# simon_SMD.net
KiCad netlist of a schematic drawn in EAGLE
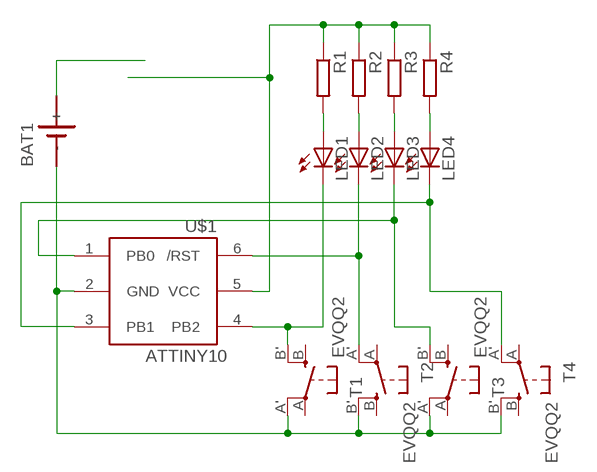
[diagram p0: schematic, sheet 1]

(export (version "E")
  (design (tool "Eeschema 10.0.6"))
  (components
    (comp (ref "BAT1")
      (value "SN2032")
      (footprint "eagle-import:SN2032")
      (libsource (lib "eagle-import") (part "SN2032"))
    )
    (comp (ref "LED1")
      (value "LEDCHIP-LED0805")
      (footprint "eagle-import:CHIP-LED0805")
      (libsource (lib "eagle-import") (part "LEDCHIP-LED0805"))
    )
    (comp (ref "LED2")
      (value "LEDCHIP-LED0805")
      (footprint "eagle-import:CHIP-LED0805")
      (libsource (lib "eagle-import") (part "LEDCHIP-LED0805"))
    )
    (comp (ref "LED3")
      (value "LEDCHIP-LED0805")
      (footprint "eagle-import:CHIP-LED0805")
      (libsource (lib "eagle-import") (part "LEDCHIP-LED0805"))
    )
    (comp (ref "LED4")
      (value "LEDCHIP-LED0805")
      (footprint "eagle-import:CHIP-LED0805")
      (libsource (lib "eagle-import") (part "LEDCHIP-LED0805"))
    )
    (comp (ref "R1")
      (value "R-EU_M0805")
      (footprint "eagle-import:M0805")
      (libsource (lib "eagle-import") (part "R-EU_M0805"))
    )
    (comp (ref "R2")
      (value "R-EU_M0805")
      (footprint "eagle-import:M0805")
      (libsource (lib "eagle-import") (part "R-EU_M0805"))
    )
    (comp (ref "R3")
      (value "R-EU_M0805")
      (footprint "eagle-import:M0805")
      (libsource (lib "eagle-import") (part "R-EU_M0805"))
    )
    (comp (ref "R4")
      (value "R-EU_M0805")
      (footprint "eagle-import:M0805")
      (libsource (lib "eagle-import") (part "R-EU_M0805"))
    )
    (comp (ref "T1")
      (value "EVQQ2")
      (footprint "eagle-import:EVQ-Q2")
      (libsource (lib "eagle-import") (part "EVQQ2"))
    )
    (comp (ref "T2")
      (value "EVQQ2")
      (footprint "eagle-import:EVQ-Q2")
      (libsource (lib "eagle-import") (part "EVQQ2"))
    )
    (comp (ref "T3")
      (value "EVQQ2")
      (footprint "eagle-import:EVQ-Q2")
      (libsource (lib "eagle-import") (part "EVQQ2"))
    )
    (comp (ref "T4")
      (value "EVQQ2")
      (footprint "eagle-import:EVQ-Q2")
      (libsource (lib "eagle-import") (part "EVQQ2"))
    )
    (comp (ref "U$1")
      (value "ATTINY10")
      (footprint "eagle-import:SOT23-6")
      (libsource (lib "eagle-import") (part "ATTINY10"))
    )
  )
  (nets
    (net (code "1") (name "Net-(LED1-PadA)") (class "Default")
      (node (ref "LED1") (pin "A") (pinfunction "A_A") (pintype "passive"))
      (node (ref "R1") (pin "2") (pinfunction "2_2") (pintype "passive"))
    )
    (net (code "2") (name "Net-(LED2-PadA)") (class "Default")
      (node (ref "LED2") (pin "A") (pinfunction "A_A") (pintype "passive"))
      (node (ref "R2") (pin "2") (pinfunction "2_2") (pintype "passive"))
    )
    (net (code "3") (name "Net-(LED3-PadA)") (class "Default")
      (node (ref "LED3") (pin "A") (pinfunction "A_A") (pintype "passive"))
      (node (ref "R3") (pin "2") (pinfunction "2_2") (pintype "passive"))
    )
    (net (code "4") (name "Net-(LED4-PadA)") (class "Default")
      (node (ref "LED4") (pin "A") (pinfunction "A_A") (pintype "passive"))
      (node (ref "R4") (pin "2") (pinfunction "2_2") (pintype "passive"))
    )
    (net (code "5") (name "Net-(T1-P1)") (class "Default")
      (node (ref "BAT1") (pin "-") (pinfunction "-_-") (pintype "passive"))
      (node (ref "T1") (pin "A'") (pinfunction "P1_A'") (pintype "passive"))
      (node (ref "T2") (pin "B'") (pinfunction "S1_B'") (pintype "passive"))
      (node (ref "T3") (pin "A'") (pinfunction "P1_A'") (pintype "passive"))
      (node (ref "T4") (pin "B'") (pinfunction "S1_B'") (pintype "passive"))
      (node (ref "U$1") (pin "2") (pinfunction "GND_2") (pintype "power_in"))
    )
    (net (code "6") (name "Net-(T1-S1)") (class "Default")
      (node (ref "LED1") (pin "C") (pinfunction "C_C") (pintype "passive"))
      (node (ref "T1") (pin "B'") (pinfunction "S1_B'") (pintype "passive"))
      (node (ref "U$1") (pin "4") (pinfunction "PB2_4") (pintype "bidirectional"))
    )
    (net (code "7") (name "Net-(T2-P1)") (class "Default")
      (node (ref "LED2") (pin "C") (pinfunction "C_C") (pintype "passive"))
      (node (ref "T2") (pin "A'") (pinfunction "P1_A'") (pintype "passive"))
      (node (ref "U$1") (pin "6") (pinfunction "/RST_6") (pintype "bidirectional"))
    )
    (net (code "8") (name "Net-(T3-S1)") (class "Default")
      (node (ref "LED3") (pin "C") (pinfunction "C_C") (pintype "passive"))
      (node (ref "T3") (pin "B'") (pinfunction "S1_B'") (pintype "passive"))
      (node (ref "U$1") (pin "1") (pinfunction "PB0_1") (pintype "bidirectional"))
    )
    (net (code "9") (name "Net-(T4-P1)") (class "Default")
      (node (ref "LED4") (pin "C") (pinfunction "C_C") (pintype "passive"))
      (node (ref "T4") (pin "A'") (pinfunction "P1_A'") (pintype "passive"))
      (node (ref "U$1") (pin "3") (pinfunction "PB1_3") (pintype "bidirectional"))
    )
    (net (code "10") (name "Net-(U$1-VCC)") (class "Default")
      (node (ref "R1") (pin "1") (pinfunction "1_1") (pintype "passive"))
      (node (ref "R2") (pin "1") (pinfunction "1_1") (pintype "passive"))
      (node (ref "R3") (pin "1") (pinfunction "1_1") (pintype "passive"))
      (node (ref "R4") (pin "1") (pinfunction "1_1") (pintype "passive"))
      (node (ref "U$1") (pin "5") (pinfunction "VCC_5") (pintype "power_in"))
    )
    (net (code "11") (name "unconnected-(BAT1-Pad+)") (class "Default")
      (node (ref "BAT1") (pin "+") (pinfunction "+_+") (pintype "passive"))
    )
    (net (code "12") (name "unconnected-(T1-P-PadA)") (class "Default")
      (node (ref "T1") (pin "A") (pinfunction "P_A") (pintype "passive"))
    )
    (net (code "13") (name "unconnected-(T1-S-PadB)") (class "Default")
      (node (ref "T1") (pin "B") (pinfunction "S_B") (pintype "passive"))
    )
    (net (code "14") (name "unconnected-(T2-P-PadA)") (class "Default")
      (node (ref "T2") (pin "A") (pinfunction "P_A") (pintype "passive"))
    )
    (net (code "15") (name "unconnected-(T2-S-PadB)") (class "Default")
      (node (ref "T2") (pin "B") (pinfunction "S_B") (pintype "passive"))
    )
    (net (code "16") (name "unconnected-(T3-P-PadA)") (class "Default")
      (node (ref "T3") (pin "A") (pinfunction "P_A") (pintype "passive"))
    )
    (net (code "17") (name "unconnected-(T3-S-PadB)") (class "Default")
      (node (ref "T3") (pin "B") (pinfunction "S_B") (pintype "passive"))
    )
    (net (code "18") (name "unconnected-(T4-P-PadA)") (class "Default")
      (node (ref "T4") (pin "A") (pinfunction "P_A") (pintype "passive"))
    )
    (net (code "19") (name "unconnected-(T4-S-PadB)") (class "Default")
      (node (ref "T4") (pin "B") (pinfunction "S_B") (pintype "passive"))
    )
  )
)
